# KNX_POE.net
KiCad netlist of a schematic drawn in Altium Designer
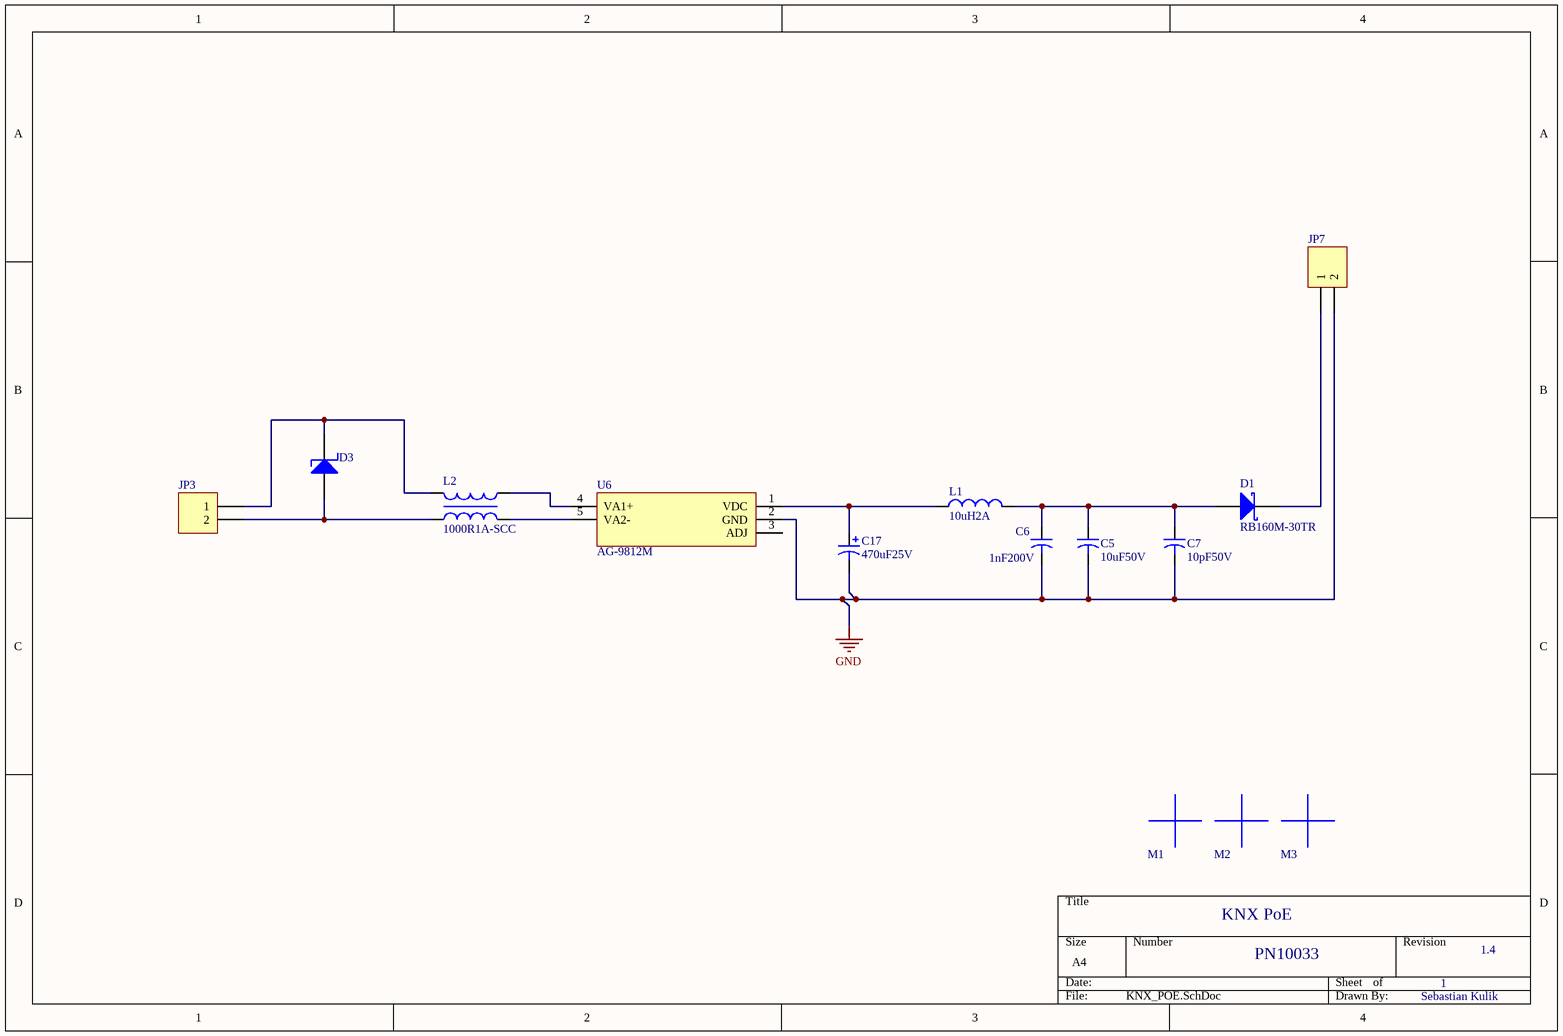
[diagram p0: KNX_POE.SchDoc]

(export (version "E")
  (design (tool "Eeschema 10.0.6"))
  (components
    (comp (ref "C5")
      (value "10uF50V")
      (footprint "C1210")
      (description "AVX,  X7R, 10%, 50V")
      (fields
        (field (name "MANUFACTURER") "AVX")
        (field (name "Comment") "10uF50V_1210")
        (field (name "PUBLISHER") "Sebastian Kulik")
      )
      (libsource (lib "Capacitors") (part "10uF50V_1210"))
    )
    (comp (ref "C6")
      (value "1nF200V")
      (footprint "C0603")
      (description "MLCC series, X7R, 10%, 200V")
      (fields
        (field (name "MANUFACTURER") "AVX")
        (field (name "Comment") "1nF200V_0603")
        (field (name "PUBLISHER") "Sebastian Kulik")
      )
      (libsource (lib "Capacitors") (part "1nF200V_0603"))
    )
    (comp (ref "C7")
      (value "10pF50V")
      (footprint "C0603")
      (description "AVX ,  +-0.5pF, 50V")
      (fields
        (field (name "MANUFACTURER") "AVX")
        (field (name "Comment") "10pF50V_0603")
        (field (name "PUBLISHER") "Sebastian Kulik")
      )
      (libsource (lib "Capacitors") (part "10pF50V_0603"))
    )
    (comp (ref "C17")
      (value "470uF25V")
      (footprint "Panasonic-FT-F_Case")
      (description "Panasonic, FT series")
      (fields
        (field (name "MANUFACTURER") "Panasonic")
        (field (name "Comment") "470uF25V_POL_FT")
        (field (name "PUBLISHER") "Sebastian Kulik")
      )
      (libsource (lib "Capacitors") (part "470uF25V_POL_FT"))
    )
    (comp (ref "D1")
      (value "RB160M-30TR")
      (footprint "SOD123")
      (description "Diode Schottky,2A,40V")
      (fields (field (name "MANUFACTURER") "Rohm") (field (name "PUBLISHER") "Sebastian Kulik"))
      (libsource (lib "Discrete") (part "RB160M-30TR"))
    )
    (comp (ref "D3")
      (value "SMAJ58A-E3/61")
      (footprint "DO214A")
      (description "TVS, 400W, 58V")
      (fields (field (name "MANUFACTURER") "Vishay") (field (name "PUBLISHER") "Sebastian Kulik"))
      (libsource (lib "Discrete") (part "SMAJ58A-E3/61"))
    )
    (comp (ref "JP3")
      (value "Plug_2_90_2.54")
      (footprint "HDR1X2-down")
      (description "Plug, 2-Pin")
      (fields (field (name "MANUFACTURER") "WE") (field (name "PUBLISHER") "Sebastian Kulik"))
      (libsource (lib "Connectors") (part "Plug_2_90_2.54"))
    )
    (comp (ref "JP7")
      (value "Plug_2_90_2.54")
      (footprint "HDR1X2-down")
      (description "Plug, 2-Pin")
      (fields (field (name "MANUFACTURER") "WE") (field (name "PUBLISHER") "Sebastian Kulik"))
      (libsource (lib "") (part "Plug_2_90_2.54_1"))
    )
    (comp (ref "L1")
      (value "10uH2A")
      (footprint "WE-PD2_1")
      (description "WE-PD2, 10uH2A")
      (fields (field (name "MANUFACTURER") "WE") (field (name "PUBLISHER") "Sebastian Kulik"))
      (libsource (lib "Passives") (part "10uH2A_WE-PD2"))
    )
    (comp (ref "L2")
      (value "1000R1A-SCC")
      (footprint "WE-SCC_7345")
      (description "Common mode choke")
      (fields (field (name "MANUFACTURER") "WE") (field (name "PUBLISHER") "Sebastian Kulik"))
      (libsource (lib "Passives") (part "1000R1A-SCC"))
    )
    (comp (ref "M1")
      (value "Paste Mark")
      (footprint "Symbols:Mark-3mm")
      (libsource (lib "Symbols") (part "Mark"))
    )
    (comp (ref "M2")
      (value "Paste Mark")
      (footprint "Symbols:Mark-3mm")
      (libsource (lib "Symbols") (part "Mark"))
    )
    (comp (ref "M3")
      (value "Paste Mark")
      (footprint "Symbols:Mark-3mm")
      (libsource (lib "Symbols") (part "Mark"))
    )
    (comp (ref "U6")
      (value "AG-9812M")
      (footprint "Ag9812M")
      (description "PoE, 12V")
      (fields (field (name "MANUFACTURER") "Silvertel") (field (name "PUBLISHER") "Sebastian Kulik"))
      (libsource (lib "ICs") (part "AG-9812M"))
    )
  )
  (nets
    (net (code "1") (name "GND") (class "Default")
      (node (ref "C17") (pin "2") (pinfunction "2_2") (pintype "passive"))
      (node (ref "C5") (pin "2") (pinfunction "2_2") (pintype "passive"))
      (node (ref "C6") (pin "2") (pinfunction "2_2") (pintype "passive"))
      (node (ref "C7") (pin "2") (pinfunction "2_2") (pintype "passive"))
      (node (ref "JP7") (pin "2") (pinfunction "2_2") (pintype "passive"))
      (node (ref "U6") (pin "2") (pinfunction "GND_2") (pintype "passive"))
    )
    (net (code "2") (name "Net-(D1-A)") (class "Default")
      (node (ref "C5") (pin "1") (pinfunction "1_1") (pintype "passive"))
      (node (ref "C6") (pin "1") (pinfunction "1_1") (pintype "passive"))
      (node (ref "C7") (pin "1") (pinfunction "1_1") (pintype "passive"))
      (node (ref "D1") (pin "2") (pinfunction "A_2") (pintype "passive"))
      (node (ref "L1") (pin "2") (pinfunction "2_2") (pintype "passive"))
    )
    (net (code "3") (name "Net-(D1-K)") (class "Default")
      (node (ref "D1") (pin "1") (pinfunction "K_1") (pintype "passive"))
      (node (ref "JP7") (pin "1") (pinfunction "1_1") (pintype "passive"))
    )
    (net (code "4") (name "Net-(D3-A)") (class "Default")
      (node (ref "D3") (pin "2") (pinfunction "A_2") (pintype "passive"))
      (node (ref "JP3") (pin "2") (pinfunction "2_2") (pintype "passive"))
      (node (ref "L2") (pin "1") (pinfunction "1_1") (pintype "passive"))
    )
    (net (code "5") (name "Net-(D3-K)") (class "Default")
      (node (ref "D3") (pin "1") (pinfunction "K_1") (pintype "passive"))
      (node (ref "JP3") (pin "1") (pinfunction "1_1") (pintype "passive"))
      (node (ref "L2") (pin "2") (pinfunction "2_2") (pintype "passive"))
    )
    (net (code "6") (name "Net-(U6-VA1+)") (class "Default")
      (node (ref "L2") (pin "4") (pinfunction "4_4") (pintype "passive"))
      (node (ref "U6") (pin "4") (pinfunction "VA1+_4") (pintype "passive"))
    )
    (net (code "7") (name "Net-(U6-VA2-)") (class "Default")
      (node (ref "L2") (pin "3") (pinfunction "3_3") (pintype "passive"))
      (node (ref "U6") (pin "5") (pinfunction "VA2-_5") (pintype "passive"))
    )
    (net (code "8") (name "Net-(U6-VDC)") (class "Default")
      (node (ref "C17") (pin "1") (pinfunction "1_1") (pintype "passive"))
      (node (ref "L1") (pin "1") (pinfunction "1_1") (pintype "passive"))
      (node (ref "U6") (pin "1") (pinfunction "VDC_1") (pintype "power_in"))
    )
    (net (code "9") (name "unconnected-(U6-ADJ-Pad3)") (class "Default")
      (node (ref "U6") (pin "3") (pinfunction "ADJ_3") (pintype "passive"))
    )
  )
)
